# MicroDStripLine.net
KiCad netlist of a schematic drawn in Altium Designer
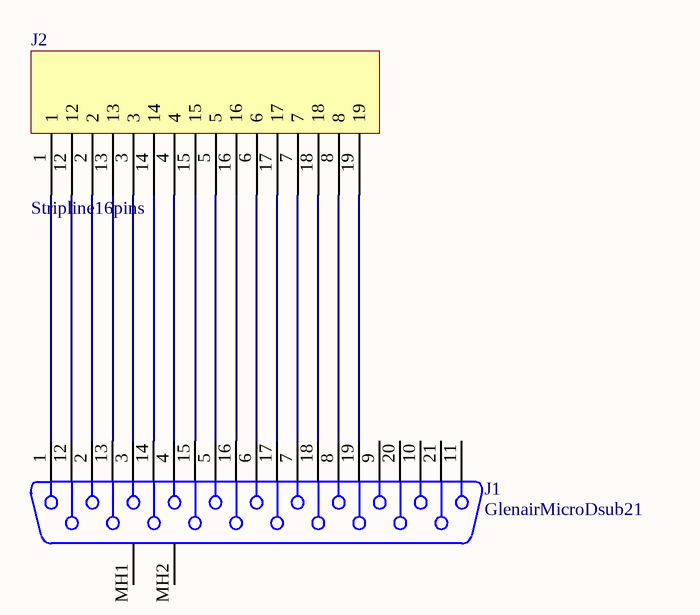
[diagram p0: MicroDStripLine.SchDoc]

(export (version "E")
  (design (tool "Eeschema 10.0.6"))
  (components
    (comp (ref "J1")
      (value "GlenairMicroDsub21")
      (footprint "MicroD21Glenair")
      (libsource (lib "AdamsParts") (part "GlenairMicroDsub21"))
    )
    (comp (ref "J2")
      (value "Stripline16pins")
      (footprint "Stripline16pins")
      (libsource (lib "AdamsParts") (part "Stripline16pins"))
    )
  )
  (nets
    (net (code "1") (name "Net-(J1-Pad1)") (class "Default")
      (node (ref "J1") (pin "1") (pinfunction "1_1") (pintype "passive"))
      (node (ref "J2") (pin "1") (pinfunction "1_1") (pintype "passive"))
    )
    (net (code "2") (name "Net-(J1-Pad2)") (class "Default")
      (node (ref "J1") (pin "2") (pinfunction "2_2") (pintype "passive"))
      (node (ref "J2") (pin "2") (pinfunction "2_2") (pintype "passive"))
    )
    (net (code "3") (name "Net-(J1-Pad3)") (class "Default")
      (node (ref "J1") (pin "3") (pinfunction "3_3") (pintype "passive"))
      (node (ref "J2") (pin "3") (pinfunction "3_3") (pintype "passive"))
    )
    (net (code "4") (name "Net-(J1-Pad4)") (class "Default")
      (node (ref "J1") (pin "4") (pinfunction "4_4") (pintype "passive"))
      (node (ref "J2") (pin "4") (pinfunction "4_4") (pintype "passive"))
    )
    (net (code "5") (name "Net-(J1-Pad5)") (class "Default")
      (node (ref "J1") (pin "5") (pinfunction "5_5") (pintype "passive"))
      (node (ref "J2") (pin "5") (pinfunction "5_5") (pintype "passive"))
    )
    (net (code "6") (name "Net-(J1-Pad6)") (class "Default")
      (node (ref "J1") (pin "6") (pinfunction "6_6") (pintype "passive"))
      (node (ref "J2") (pin "6") (pinfunction "6_6") (pintype "passive"))
    )
    (net (code "7") (name "Net-(J1-Pad7)") (class "Default")
      (node (ref "J1") (pin "7") (pinfunction "7_7") (pintype "passive"))
      (node (ref "J2") (pin "7") (pinfunction "7_7") (pintype "passive"))
    )
    (net (code "8") (name "Net-(J1-Pad8)") (class "Default")
      (node (ref "J1") (pin "8") (pinfunction "8_8") (pintype "passive"))
      (node (ref "J2") (pin "8") (pinfunction "8_8") (pintype "passive"))
    )
    (net (code "9") (name "Net-(J1-Pad12)") (class "Default")
      (node (ref "J1") (pin "12") (pinfunction "12_12") (pintype "passive"))
      (node (ref "J2") (pin "12") (pinfunction "12_12") (pintype "passive"))
    )
    (net (code "10") (name "Net-(J1-Pad13)") (class "Default")
      (node (ref "J1") (pin "13") (pinfunction "13_13") (pintype "passive"))
      (node (ref "J2") (pin "13") (pinfunction "13_13") (pintype "passive"))
    )
    (net (code "11") (name "Net-(J1-Pad14)") (class "Default")
      (node (ref "J1") (pin "14") (pinfunction "14_14") (pintype "passive"))
      (node (ref "J2") (pin "14") (pinfunction "14_14") (pintype "passive"))
    )
    (net (code "12") (name "Net-(J1-Pad15)") (class "Default")
      (node (ref "J1") (pin "15") (pinfunction "15_15") (pintype "passive"))
      (node (ref "J2") (pin "15") (pinfunction "15_15") (pintype "passive"))
    )
    (net (code "13") (name "Net-(J1-Pad16)") (class "Default")
      (node (ref "J1") (pin "16") (pinfunction "16_16") (pintype "passive"))
      (node (ref "J2") (pin "16") (pinfunction "16_16") (pintype "passive"))
    )
    (net (code "14") (name "Net-(J1-Pad17)") (class "Default")
      (node (ref "J1") (pin "17") (pinfunction "17_17") (pintype "passive"))
      (node (ref "J2") (pin "17") (pinfunction "17_17") (pintype "passive"))
    )
    (net (code "15") (name "Net-(J1-Pad18)") (class "Default")
      (node (ref "J1") (pin "18") (pinfunction "18_18") (pintype "passive"))
      (node (ref "J2") (pin "18") (pinfunction "18_18") (pintype "passive"))
    )
    (net (code "16") (name "Net-(J1-Pad19)") (class "Default")
      (node (ref "J1") (pin "19") (pinfunction "19_19") (pintype "passive"))
      (node (ref "J2") (pin "19") (pinfunction "19_19") (pintype "passive"))
    )
    (net (code "17") (name "unconnected-(J1-Pad9)") (class "Default")
      (node (ref "J1") (pin "9") (pinfunction "9_9") (pintype "passive"))
    )
    (net (code "18") (name "unconnected-(J1-Pad10)") (class "Default")
      (node (ref "J1") (pin "10") (pinfunction "10_10") (pintype "passive"))
    )
    (net (code "19") (name "unconnected-(J1-Pad11)") (class "Default")
      (node (ref "J1") (pin "11") (pinfunction "11_11") (pintype "passive"))
    )
    (net (code "20") (name "unconnected-(J1-Pad20)") (class "Default")
      (node (ref "J1") (pin "20") (pinfunction "20_20") (pintype "passive"))
    )
    (net (code "21") (name "unconnected-(J1-Pad21)") (class "Default")
      (node (ref "J1") (pin "21") (pinfunction "21_21") (pintype "passive"))
    )
    (net (code "22") (name "unconnected-(J1-PadMH1)") (class "Default")
      (node (ref "J1") (pin "MH1") (pinfunction "MH1_MH1") (pintype "passive"))
    )
    (net (code "23") (name "unconnected-(J1-PadMH2)") (class "Default")
      (node (ref "J1") (pin "MH2") (pinfunction "MH2_MH2") (pintype "passive"))
    )
  )
)
